# Screen.net
KiCad netlist of a schematic drawn in Altium Designer
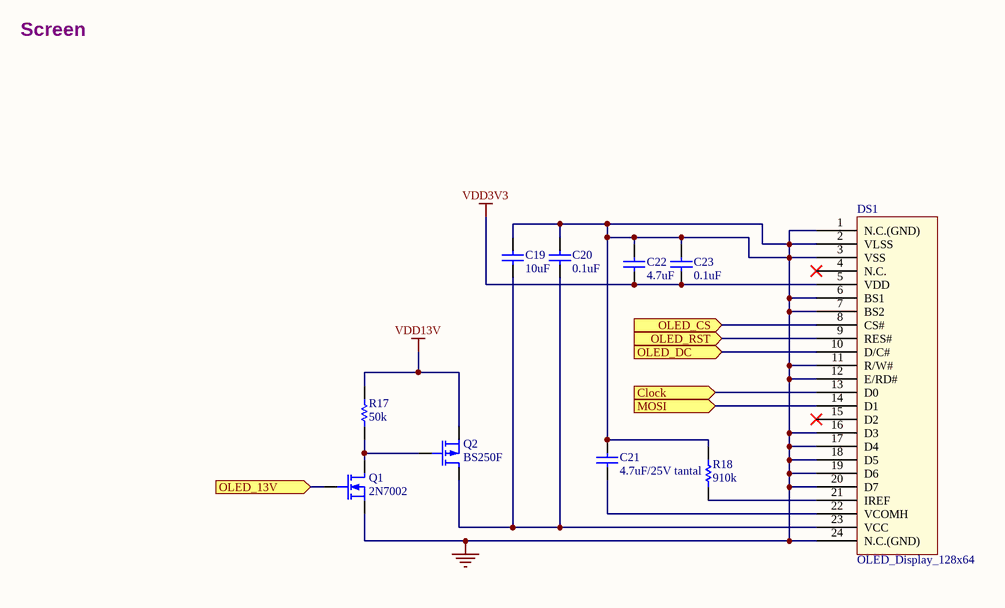
[diagram p0: Screen.SchDoc]

(export (version "E")
  (design (tool "Eeschema 10.0.6"))
  (components
    (comp (ref "C19")
      (value "10uF")
      (footprint "CAPC1608X90N")
      (description "Capacitor")
      (libsource (lib "POP_lib") (part "Capacitor"))
    )
    (comp (ref "C20")
      (value "0.1uF")
      (footprint "CAPC1608X90N")
      (description "Capacitor")
      (libsource (lib "POP_lib") (part "Capacitor"))
    )
    (comp (ref "C21")
      (value "4.7uF/25V tantal")
      (footprint "CAPMP3216X180N")
      (description "Capacitor")
      (libsource (lib "POP_lib") (part "Capacitor"))
    )
    (comp (ref "C22")
      (value "4.7uF")
      (footprint "CAPC2012X135N")
      (description "Capacitor")
      (libsource (lib "POP_lib") (part "Capacitor"))
    )
    (comp (ref "C23")
      (value "0.1uF")
      (footprint "CAPC2012X135N")
      (description "Capacitor")
      (libsource (lib "POP_lib") (part "Capacitor"))
    )
    (comp (ref "DS1")
      (value "OLED_Display_128x64")
      (footprint "HRS_FH12-24S-0.5SH(55)")
      (libsource (lib "POP_lib") (part "OLED_Display_128x64"))
    )
    (comp (ref "Q1")
      (value "2N7002")
      (footprint "SOT23-3")
      (description "N-Channel MOSFET")
      (libsource (lib "POP_lib") (part "MOSFET-N"))
    )
    (comp (ref "Q2")
      (value "BS250F")
      (footprint "SOT23-3")
      (description "P-Channel MOSFET")
      (libsource (lib "POP_lib") (part "MOSFET-P"))
    )
    (comp (ref "R17")
      (value "50k")
      (footprint "RESC1608X55N")
      (description "Resistor")
      (libsource (lib "POP_lib") (part "Resistor"))
    )
    (comp (ref "R18")
      (value "910k")
      (footprint "RESC1608X55N")
      (description "Resistor")
      (libsource (lib "POP_lib") (part "Resistor"))
    )
  )
  (nets
    (net (code "1") (name "/Clock") (class "Default")
      (node (ref "DS1") (pin "13") (pinfunction "D0_13") (pintype "passive"))
    )
    (net (code "2") (name "/MOSI") (class "Default")
      (node (ref "DS1") (pin "14") (pinfunction "D1_14") (pintype "passive"))
    )
    (net (code "3") (name "/OLED_13V") (class "Default")
      (node (ref "Q1") (pin "1") (pinfunction "G_1") (pintype "passive"))
    )
    (net (code "4") (name "/OLED_CS") (class "Default")
      (node (ref "DS1") (pin "8") (pinfunction "CS#_8") (pintype "passive"))
    )
    (net (code "5") (name "/OLED_DC") (class "Default")
      (node (ref "DS1") (pin "10") (pinfunction "D/C#_10") (pintype "passive"))
    )
    (net (code "6") (name "/OLED_RST") (class "Default")
      (node (ref "DS1") (pin "9") (pinfunction "RES#_9") (pintype "passive"))
    )
    (net (code "7") (name "GND") (class "Default")
      (node (ref "C19") (pin "2") (pinfunction "2_2") (pintype "passive"))
      (node (ref "C20") (pin "1") (pinfunction "1_1") (pintype "passive"))
      (node (ref "C21") (pin "1") (pinfunction "1_1") (pintype "passive"))
      (node (ref "C22") (pin "2") (pinfunction "2_2") (pintype "passive"))
      (node (ref "C23") (pin "1") (pinfunction "1_1") (pintype "passive"))
      (node (ref "DS1") (pin "1") (pinfunction "N.C.(GND)_1") (pintype "passive"))
      (node (ref "DS1") (pin "11") (pinfunction "R/W#_11") (pintype "passive"))
      (node (ref "DS1") (pin "12") (pinfunction "E/RD#_12") (pintype "passive"))
      (node (ref "DS1") (pin "16") (pinfunction "D3_16") (pintype "passive"))
      (node (ref "DS1") (pin "17") (pinfunction "D4_17") (pintype "passive"))
      (node (ref "DS1") (pin "18") (pinfunction "D5_18") (pintype "passive"))
      (node (ref "DS1") (pin "19") (pinfunction "D6_19") (pintype "passive"))
      (node (ref "DS1") (pin "2") (pinfunction "VLSS_2") (pintype "passive"))
      (node (ref "DS1") (pin "20") (pinfunction "D7_20") (pintype "passive"))
      (node (ref "DS1") (pin "24") (pinfunction "N.C.(GND)_24") (pintype "passive"))
      (node (ref "DS1") (pin "3") (pinfunction "VSS_3") (pintype "passive"))
      (node (ref "DS1") (pin "6") (pinfunction "BS1_6") (pintype "passive"))
      (node (ref "DS1") (pin "7") (pinfunction "BS2_7") (pintype "passive"))
      (node (ref "Q1") (pin "2") (pinfunction "S_2") (pintype "passive"))
      (node (ref "R18") (pin "1") (pinfunction "1_1") (pintype "passive"))
    )
    (net (code "8") (name "Net-(DS1-IREF)") (class "Default")
      (node (ref "DS1") (pin "21") (pinfunction "IREF_21") (pintype "passive"))
      (node (ref "R18") (pin "2") (pinfunction "2_2") (pintype "passive"))
    )
    (net (code "9") (name "Net-(DS1-VCC)") (class "Default")
      (node (ref "C19") (pin "1") (pinfunction "1_1") (pintype "passive"))
      (node (ref "C20") (pin "2") (pinfunction "2_2") (pintype "passive"))
      (node (ref "DS1") (pin "23") (pinfunction "VCC_23") (pintype "passive"))
      (node (ref "Q2") (pin "3") (pinfunction "D_3") (pintype "passive"))
    )
    (net (code "10") (name "Net-(DS1-VCOMH)") (class "Default")
      (node (ref "C21") (pin "2") (pinfunction "2_2") (pintype "passive"))
      (node (ref "DS1") (pin "22") (pinfunction "VCOMH_22") (pintype "passive"))
    )
    (net (code "11") (name "Net-(Q1-D)") (class "Default")
      (node (ref "Q1") (pin "3") (pinfunction "D_3") (pintype "passive"))
      (node (ref "Q2") (pin "1") (pinfunction "G_1") (pintype "passive"))
      (node (ref "R17") (pin "1") (pinfunction "1_1") (pintype "passive"))
    )
    (net (code "12") (name "VDD3V3") (class "Default")
      (node (ref "C22") (pin "1") (pinfunction "1_1") (pintype "passive"))
      (node (ref "C23") (pin "2") (pinfunction "2_2") (pintype "passive"))
      (node (ref "DS1") (pin "5") (pinfunction "VDD_5") (pintype "passive"))
    )
    (net (code "13") (name "VDD13V") (class "Default")
      (node (ref "Q2") (pin "2") (pinfunction "S_2") (pintype "passive"))
      (node (ref "R17") (pin "2") (pinfunction "2_2") (pintype "passive"))
    )
    (net (code "14") (name "unconnected-(DS1-D2-Pad15)") (class "Default")
      (node (ref "DS1") (pin "15") (pinfunction "D2_15") (pintype "passive+no_connect"))
    )
    (net (code "15") (name "unconnected-(DS1-N.C.-Pad4)") (class "Default")
      (node (ref "DS1") (pin "4") (pinfunction "N.C._4") (pintype "passive+no_connect"))
    )
  )
)
